# can.net
KiCad netlist of a schematic drawn in Altium Designer
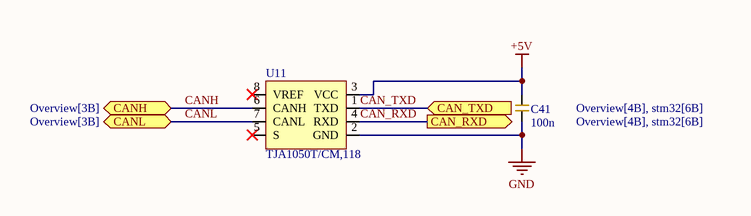
[diagram p0: can.SchDoc]

(export (version "E")
  (design (tool "Eeschema 10.0.6"))
  (components
    (comp (ref "C41")
      (value "100n")
      (footprint "CAP_0603")
      (description "Multilayer Ceramic Capacitors MLCC - SMD/SMT ROHS")
      (libsource (lib "Passive") (part "CAP_0603"))
    )
    (comp (ref "U11")
      (value "TJA1050T/CM,118")
      (footprint "TJA1050T/CM,118")
      (description "SOP-8 CAN Transceivers ROHS")
      (fields (field (name "MFR.") "NXP Semicon"))
      (libsource (lib "ICs") (part "TJA1050T/CM,118"))
    )
  )
  (nets
    (net (code "1") (name "+5V") (class "Default")
      (node (ref "C41") (pin "2") (pintype "passive"))
      (node (ref "U11") (pin "3") (pinfunction "VCC_3") (pintype "passive"))
    )
    (net (code "2") (name "/CANH") (class "Default")
      (node (ref "U11") (pin "6") (pinfunction "CANH_6") (pintype "passive"))
    )
    (net (code "3") (name "/CANL") (class "Default")
      (node (ref "U11") (pin "7") (pinfunction "CANL_7") (pintype "passive"))
    )
    (net (code "4") (name "/CAN_RXD") (class "Default")
      (node (ref "U11") (pin "4") (pinfunction "RXD_4") (pintype "passive"))
    )
    (net (code "5") (name "/CAN_TXD") (class "Default")
      (node (ref "U11") (pin "1") (pinfunction "TXD_1") (pintype "passive"))
    )
    (net (code "6") (name "GND") (class "Default")
      (node (ref "C41") (pin "1") (pintype "passive"))
      (node (ref "U11") (pin "2") (pinfunction "GND_2") (pintype "passive"))
    )
    (net (code "7") (name "unconnected-(U11-S-Pad5)") (class "Default")
      (node (ref "U11") (pin "5") (pinfunction "S_5") (pintype "passive+no_connect"))
    )
    (net (code "8") (name "unconnected-(U11-VREF-Pad8)") (class "Default")
      (node (ref "U11") (pin "8") (pinfunction "VREF_8") (pintype "passive+no_connect"))
    )
  )
)
